# UI.net
KiCad netlist of a schematic drawn in Altium Designer
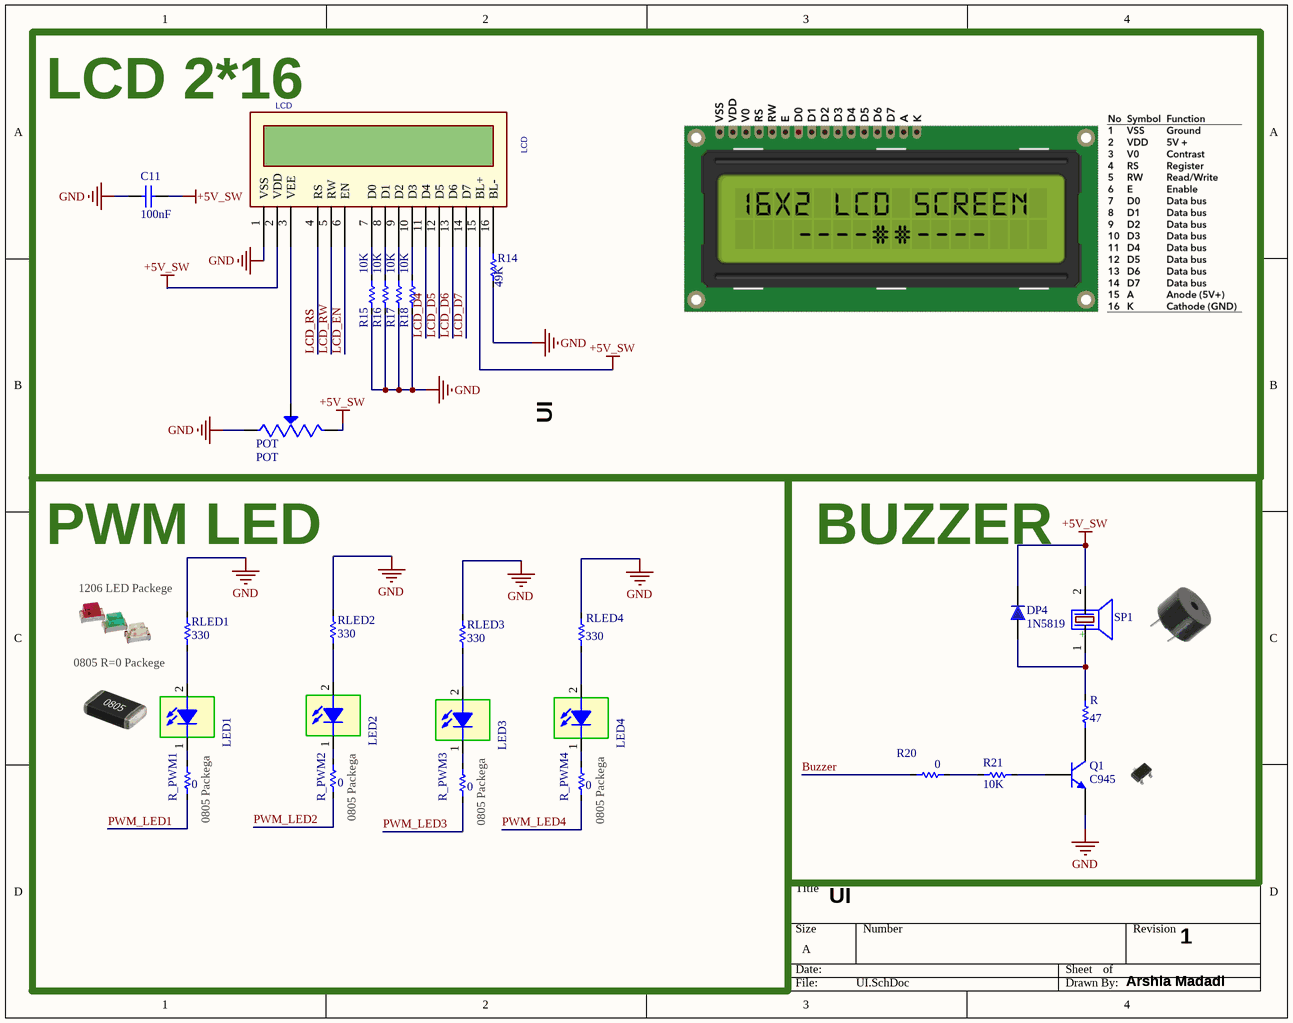
[diagram p0: UI.SchDoc]

(export (version "E")
  (design (tool "Eeschema 10.0.6"))
  (components
    (comp (ref "C11")
      (value "100nF")
      (footprint "CAPC4817X12N")
      (description "CAP 1206")
      (fields (field (name "DESIGNER") "Abbas Basereh"))
      (libsource (lib "Altium") (part "CAP SMD 1206"))
    )
    (comp (ref "DP4")
      (value "1N5819")
      (footprint "430X270D")
      (description "Schottkey Rectifiers")
      (fields (field (name "DESIGNER") "Abbas Basereh"))
      (libsource (lib "Altium") (part "1N5819"))
    )
    (comp (ref "LCD")
      (value "LCD")
      (footprint "LCD_2X16 BLUE - 2.5mm")
      (description "Alphanumic LCD")
      (fields (field (name "DESIGNER") "Abbas Basereh"))
      (libsource (lib "Altium") (part "LCD"))
    )
    (comp (ref "LED1")
      (value "SMD 1206 LED")
      (footprint "LED 1206")
      (libsource (lib "Altium") (part "LED SMD 1206"))
    )
    (comp (ref "LED2")
      (value "SMD 1206 LED")
      (footprint "LED 1206")
      (libsource (lib "Altium") (part "LED SMD 1206"))
    )
    (comp (ref "LED3")
      (value "SMD 1206 LED")
      (footprint "LED 1206")
      (libsource (lib "Altium") (part "LED SMD 1206"))
    )
    (comp (ref "LED4")
      (value "SMD 1206 LED")
      (footprint "LED 1206")
      (libsource (lib "Altium") (part "LED SMD 1206"))
    )
    (comp (ref "POT")
      (value "POT")
      (footprint "TRIM_3296W1103LF")
      (description "Trimmer, Potentiometer 10kohm 25turn Thd")
      (fields (field (name "MP") "3296W1103LF") (field (name "MF") "Bourns"))
      (libsource (lib "Multi Turn 3296W-1-103LF") (part "3296W1103LF"))
    )
    (comp (ref "Q1")
      (value "C945")
      (footprint "SOT23_M")
      (description "NPN Silicon Epitaxial Planar Transistor")
      (fields (field (name "PUBLISHER") "Abbas Basereh"))
      (libsource (lib "Altium") (part "C945"))
    )
    (comp (ref "R")
      (value "47")
      (footprint "1206_Res")
      (description "Resistor")
      (fields (field (name "PUBLISHER") "Altium Limited"))
      (libsource (lib "Sajad_Altium_Library") (part "Res"))
    )
    (comp (ref "R14")
      (value "49K")
      (footprint "1206_Res")
      (description "Resistor")
      (fields (field (name "PUBLISHER") "Altium Limited"))
      (libsource (lib "Sajad_Altium_Library") (part "Res"))
    )
    (comp (ref "R15")
      (value "10K")
      (footprint "1206_Res")
      (description "Resistor")
      (fields (field (name "PUBLISHER") "Altium Limited"))
      (libsource (lib "Sajad_Altium_Library") (part "Res"))
    )
    (comp (ref "R16")
      (value "10K")
      (footprint "1206_Res")
      (description "Resistor")
      (fields (field (name "PUBLISHER") "Altium Limited"))
      (libsource (lib "Sajad_Altium_Library") (part "Res"))
    )
    (comp (ref "R17")
      (value "10K")
      (footprint "1206_Res")
      (description "Resistor")
      (fields (field (name "PUBLISHER") "Altium Limited"))
      (libsource (lib "Sajad_Altium_Library") (part "Res"))
    )
    (comp (ref "R18")
      (value "10K")
      (footprint "1206_Res")
      (description "Resistor")
      (fields (field (name "PUBLISHER") "Altium Limited"))
      (libsource (lib "Sajad_Altium_Library") (part "Res"))
    )
    (comp (ref "R20")
      (value "0")
      (footprint "0805")
      (description "Resistor")
      (fields (field (name "PUBLISHER") "Altium Limited"))
      (libsource (lib "Sajad_Altium_Library") (part "Res"))
    )
    (comp (ref "R21")
      (value "10K")
      (footprint "1206_Res")
      (description "Resistor")
      (fields (field (name "PUBLISHER") "Altium Limited"))
      (libsource (lib "Sajad_Altium_Library") (part "Res"))
    )
    (comp (ref "RLED1")
      (value "330")
      (footprint "1206_Res")
      (description "Resistor")
      (fields (field (name "PUBLISHER") "Altium Limited"))
      (libsource (lib "Sajad_Altium_Library") (part "Res"))
    )
    (comp (ref "RLED2")
      (value "330")
      (footprint "1206_Res")
      (description "Resistor")
      (fields (field (name "PUBLISHER") "Altium Limited"))
      (libsource (lib "Sajad_Altium_Library") (part "Res"))
    )
    (comp (ref "RLED3")
      (value "330")
      (footprint "1206_Res")
      (description "Resistor")
      (fields (field (name "PUBLISHER") "Altium Limited"))
      (libsource (lib "Sajad_Altium_Library") (part "Res"))
    )
    (comp (ref "RLED4")
      (value "330")
      (footprint "1206_Res")
      (description "Resistor")
      (fields (field (name "PUBLISHER") "Altium Limited"))
      (libsource (lib "Sajad_Altium_Library") (part "Res"))
    )
    (comp (ref "R_PWM1")
      (value "0")
      (footprint "0805")
      (description "Resistor")
      (fields (field (name "PUBLISHER") "Altium Limited"))
      (libsource (lib "Sajad_Altium_Library") (part "Res"))
    )
    (comp (ref "R_PWM2")
      (value "0")
      (footprint "0805")
      (description "Resistor")
      (fields (field (name "PUBLISHER") "Altium Limited"))
      (libsource (lib "Sajad_Altium_Library") (part "Res"))
    )
    (comp (ref "R_PWM3")
      (value "0")
      (footprint "0805")
      (description "Resistor")
      (fields (field (name "PUBLISHER") "Altium Limited"))
      (libsource (lib "Sajad_Altium_Library") (part "Res"))
    )
    (comp (ref "R_PWM4")
      (value "0")
      (footprint "0805")
      (description "Resistor")
      (fields (field (name "PUBLISHER") "Altium Limited"))
      (libsource (lib "Sajad_Altium_Library") (part "Res"))
    )
    (comp (ref "SP1")
      (value "~")
      (footprint "BUZZER 7.62mm DC")
      (description "PIEZO BUZZER ACTIVE")
      (fields (field (name "DESIGNER") "Abbas Basereh") (field (name "PUBLISHER") "Abbas Basereh"))
      (libsource (lib "Altium") (part "PIEZO BUZZER"))
    )
  )
  (nets
    (net (code "1") (name "+5V_SW") (class "Default")
      (node (ref "C11") (pin "2") (pinfunction "2_2") (pintype "passive"))
      (node (ref "DP4") (pin "2") (pintype "passive"))
      (node (ref "LCD") (pin "15") (pinfunction "BL+_15") (pintype "passive"))
      (node (ref "LCD") (pin "2") (pinfunction "VDD_2") (pintype "passive"))
      (node (ref "POT") (pin "3") (pinfunction "CW_3") (pintype "passive"))
      (node (ref "SP1") (pin "2") (pinfunction "-_2") (pintype "passive"))
    )
    (net (code "2") (name "/Buzzer") (class "Default")
      (node (ref "R20") (pin "2") (pinfunction "2_2") (pintype "passive"))
    )
    (net (code "3") (name "/LCD_D4") (class "Default")
      (node (ref "LCD") (pin "11") (pinfunction "D4_11") (pintype "passive"))
    )
    (net (code "4") (name "/LCD_D5") (class "Default")
      (node (ref "LCD") (pin "12") (pinfunction "D5_12") (pintype "passive"))
    )
    (net (code "5") (name "/LCD_D6") (class "Default")
      (node (ref "LCD") (pin "13") (pinfunction "D6_13") (pintype "passive"))
    )
    (net (code "6") (name "/LCD_D7") (class "Default")
      (node (ref "LCD") (pin "14") (pinfunction "D7_14") (pintype "passive"))
    )
    (net (code "7") (name "/LCD_EN") (class "Default")
      (node (ref "LCD") (pin "6") (pinfunction "EN_6") (pintype "passive"))
    )
    (net (code "8") (name "/LCD_RS") (class "Default")
      (node (ref "LCD") (pin "4") (pinfunction "RS_4") (pintype "passive"))
    )
    (net (code "9") (name "/LCD_RW") (class "Default")
      (node (ref "LCD") (pin "5") (pinfunction "RW_5") (pintype "passive"))
    )
    (net (code "10") (name "/PWM_LED1") (class "Default")
      (node (ref "R_PWM1") (pin "1") (pinfunction "1_1") (pintype "passive"))
    )
    (net (code "11") (name "/PWM_LED2") (class "Default")
      (node (ref "R_PWM2") (pin "1") (pinfunction "1_1") (pintype "passive"))
    )
    (net (code "12") (name "/PWM_LED3") (class "Default")
      (node (ref "R_PWM3") (pin "1") (pinfunction "1_1") (pintype "passive"))
    )
    (net (code "13") (name "/PWM_LED4") (class "Default")
      (node (ref "R_PWM4") (pin "1") (pinfunction "1_1") (pintype "passive"))
    )
    (net (code "14") (name "GND") (class "Default")
      (node (ref "C11") (pin "1") (pinfunction "1_1") (pintype "passive"))
      (node (ref "LCD") (pin "1") (pinfunction "VSS_1") (pintype "passive"))
      (node (ref "POT") (pin "1") (pinfunction "CCW_1") (pintype "passive"))
      (node (ref "Q1") (pin "2") (pinfunction "E_2") (pintype "passive"))
      (node (ref "R14") (pin "2") (pinfunction "2_2") (pintype "passive"))
      (node (ref "R15") (pin "1") (pinfunction "1_1") (pintype "passive"))
      (node (ref "R16") (pin "1") (pinfunction "1_1") (pintype "passive"))
      (node (ref "R17") (pin "1") (pinfunction "1_1") (pintype "passive"))
      (node (ref "R18") (pin "1") (pinfunction "1_1") (pintype "passive"))
      (node (ref "RLED1") (pin "2") (pinfunction "2_2") (pintype "passive"))
      (node (ref "RLED2") (pin "2") (pinfunction "2_2") (pintype "passive"))
      (node (ref "RLED3") (pin "2") (pinfunction "2_2") (pintype "passive"))
      (node (ref "RLED4") (pin "2") (pinfunction "2_2") (pintype "passive"))
    )
    (net (code "15") (name "Net-(LCD-BL-)") (class "Default")
      (node (ref "LCD") (pin "16") (pinfunction "BL-_16") (pintype "passive"))
      (node (ref "R14") (pin "1") (pinfunction "1_1") (pintype "passive"))
    )
    (net (code "16") (name "Net-(LCD-D0)") (class "Default")
      (node (ref "LCD") (pin "7") (pinfunction "D0_7") (pintype "passive"))
      (node (ref "R15") (pin "2") (pinfunction "2_2") (pintype "passive"))
    )
    (net (code "17") (name "Net-(LCD-D1)") (class "Default")
      (node (ref "LCD") (pin "8") (pinfunction "D1_8") (pintype "passive"))
      (node (ref "R16") (pin "2") (pinfunction "2_2") (pintype "passive"))
    )
    (net (code "18") (name "Net-(LCD-D2)") (class "Default")
      (node (ref "LCD") (pin "9") (pinfunction "D2_9") (pintype "passive"))
      (node (ref "R17") (pin "2") (pinfunction "2_2") (pintype "passive"))
    )
    (net (code "19") (name "Net-(LCD-D3)") (class "Default")
      (node (ref "LCD") (pin "10") (pinfunction "D3_10") (pintype "passive"))
      (node (ref "R18") (pin "2") (pinfunction "2_2") (pintype "passive"))
    )
    (net (code "20") (name "Net-(LCD-VEE)") (class "Default")
      (node (ref "LCD") (pin "3") (pinfunction "VEE_3") (pintype "passive"))
      (node (ref "POT") (pin "2") (pinfunction "WIPER_2") (pintype "passive"))
    )
    (net (code "21") (name "Net-(LED1-Pad1)") (class "Default")
      (node (ref "LED1") (pin "1") (pinfunction "1_1") (pintype "passive"))
      (node (ref "R_PWM1") (pin "2") (pinfunction "2_2") (pintype "passive"))
    )
    (net (code "22") (name "Net-(LED1-Pad2)") (class "Default")
      (node (ref "LED1") (pin "2") (pinfunction "2_2") (pintype "passive"))
      (node (ref "RLED1") (pin "1") (pinfunction "1_1") (pintype "passive"))
    )
    (net (code "23") (name "Net-(LED2-Pad1)") (class "Default")
      (node (ref "LED2") (pin "1") (pinfunction "1_1") (pintype "passive"))
      (node (ref "R_PWM2") (pin "2") (pinfunction "2_2") (pintype "passive"))
    )
    (net (code "24") (name "Net-(LED2-Pad2)") (class "Default")
      (node (ref "LED2") (pin "2") (pinfunction "2_2") (pintype "passive"))
      (node (ref "RLED2") (pin "1") (pinfunction "1_1") (pintype "passive"))
    )
    (net (code "25") (name "Net-(LED3-Pad1)") (class "Default")
      (node (ref "LED3") (pin "1") (pinfunction "1_1") (pintype "passive"))
      (node (ref "R_PWM3") (pin "2") (pinfunction "2_2") (pintype "passive"))
    )
    (net (code "26") (name "Net-(LED3-Pad2)") (class "Default")
      (node (ref "LED3") (pin "2") (pinfunction "2_2") (pintype "passive"))
      (node (ref "RLED3") (pin "1") (pinfunction "1_1") (pintype "passive"))
    )
    (net (code "27") (name "Net-(LED4-Pad1)") (class "Default")
      (node (ref "LED4") (pin "1") (pinfunction "1_1") (pintype "passive"))
      (node (ref "R_PWM4") (pin "2") (pinfunction "2_2") (pintype "passive"))
    )
    (net (code "28") (name "Net-(LED4-Pad2)") (class "Default")
      (node (ref "LED4") (pin "2") (pinfunction "2_2") (pintype "passive"))
      (node (ref "RLED4") (pin "1") (pinfunction "1_1") (pintype "passive"))
    )
    (net (code "29") (name "Net-(Q1-B)") (class "Default")
      (node (ref "Q1") (pin "1") (pinfunction "B_1") (pintype "passive"))
      (node (ref "R21") (pin "1") (pinfunction "1_1") (pintype "passive"))
    )
    (net (code "30") (name "Net-(Q1-C)") (class "Default")
      (node (ref "Q1") (pin "3") (pinfunction "C_3") (pintype "passive"))
      (node (ref "R") (pin "1") (pinfunction "1_1") (pintype "passive"))
    )
    (net (code "31") (name "Net-(R20-Pad1)") (class "Default")
      (node (ref "R20") (pin "1") (pinfunction "1_1") (pintype "passive"))
      (node (ref "R21") (pin "2") (pinfunction "2_2") (pintype "passive"))
    )
    (net (code "32") (name "Net-(SP1-+)") (class "Default")
      (node (ref "DP4") (pin "1") (pintype "passive"))
      (node (ref "R") (pin "2") (pinfunction "2_2") (pintype "passive"))
      (node (ref "SP1") (pin "1") (pinfunction "+_1") (pintype "passive"))
    )
  )
)
